# Heated_Bed_Controller.net
KiCad netlist of a schematic drawn in Altium Designer
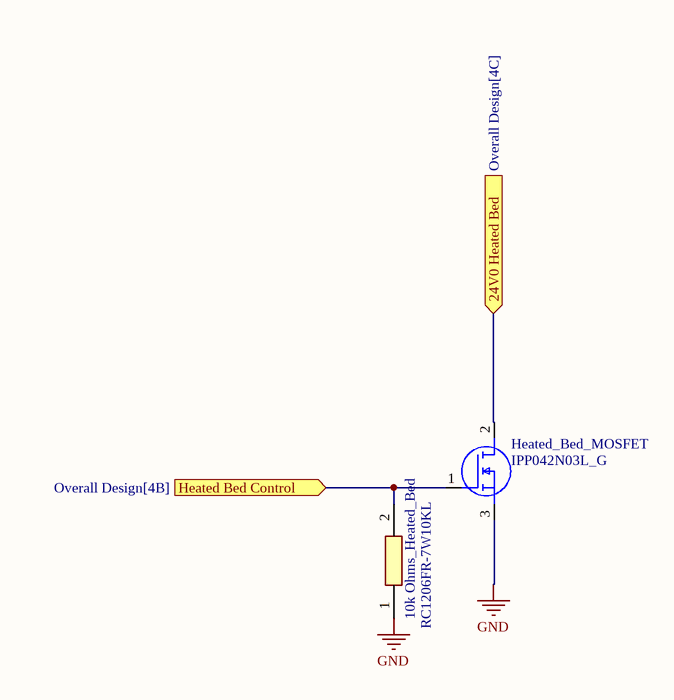
[diagram p0: Heated Bed Controller.SchDoc]

(export (version "E")
  (design (tool "Eeschema 10.0.6"))
  (components
    (comp (ref "10k Ohms_Heated_Bed")
      (value "RC1206FR-7W10KL")
      (footprint "SamacSys:RESC3116X65N")
      (description "Resistor")
      (libsource (lib "*") (part "RC1206FR-7W10KL"))
    )
    (comp (ref "Heated_Bed_MOSFET")
      (value "IPP042N03L_G")
      (footprint "SamacSys:TO254P457X1003X2115-3P")
      (description "MOSFET (N-Channel)")
      (fields
        (field (name "MANUFACTURER_PART_NUMBER") "IPP042N03L G")
        (field (name "MOUSER PART NUMBER") "726-IPP042N03LG")
      )
      (libsource (lib "*") (part "IPP042N03L_G"))
    )
  )
  (nets
    (net (code "1") (name "/24V0 Heated Bed") (class "Default")
      (node (ref "Heated_Bed_MOSFET") (pin "2") (pinfunction "D_2") (pintype "passive"))
    )
    (net (code "2") (name "/Heated Bed Control") (class "Default")
      (node (ref "10k Ohms_Heated_Bed") (pin "2") (pinfunction "2_2") (pintype "passive"))
      (node (ref "Heated_Bed_MOSFET") (pin "1") (pinfunction "G_1") (pintype "passive"))
    )
    (net (code "3") (name "GND") (class "Default")
      (node (ref "10k Ohms_Heated_Bed") (pin "1") (pinfunction "1_1") (pintype "passive"))
      (node (ref "Heated_Bed_MOSFET") (pin "3") (pinfunction "S_3") (pintype "passive"))
    )
  )
)
